# attiny85-mini-mk-2_1.net
KiCad netlist of a schematic drawn in EAGLE
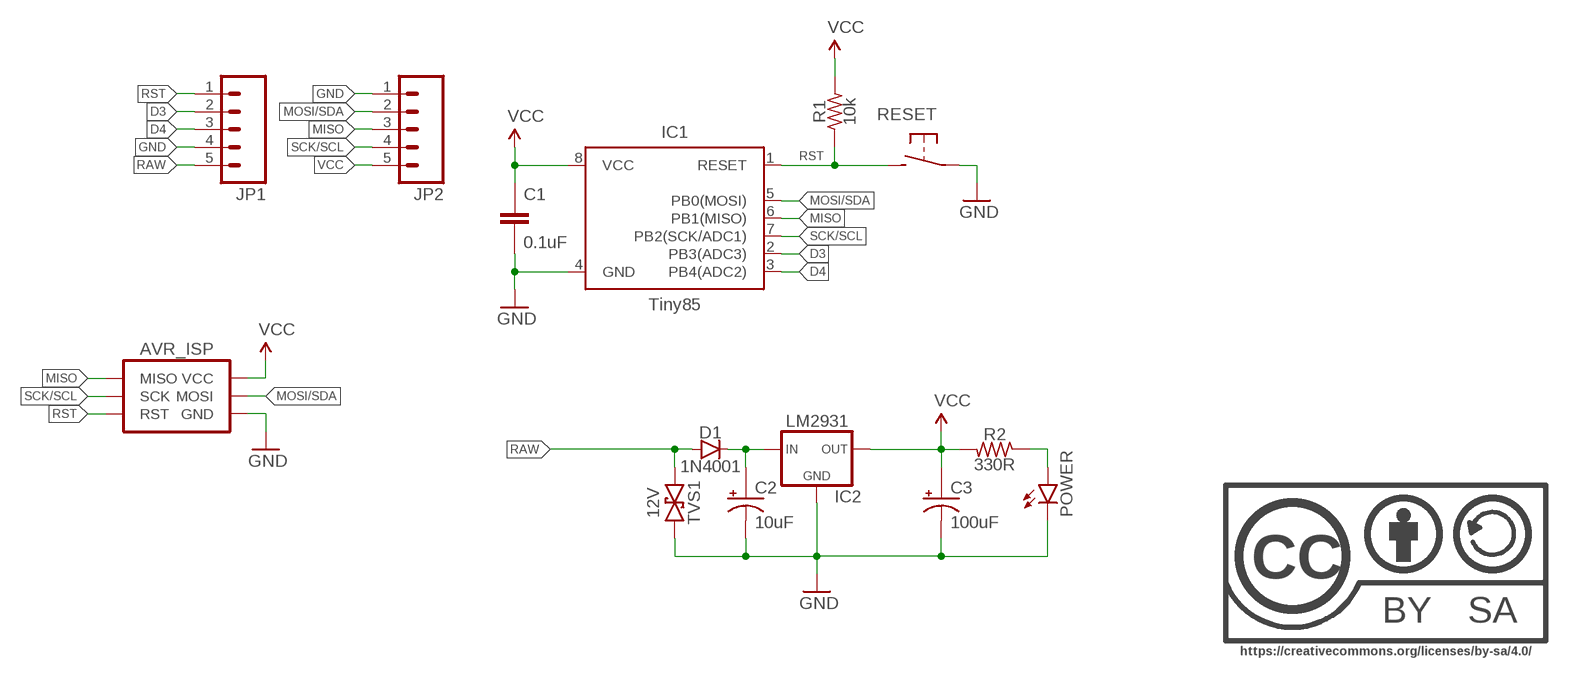
[diagram p0: schematic, sheet 1]

(export (version "E")
  (design (tool "Eeschema 10.0.6"))
  (components
    (comp (ref "AVR_ISP")
      (value "AVR_SPI_PRG_6PTH")
      (footprint "eagle-import:2X3")
      (libsource (lib "eagle-import") (part "AVR_SPI_PRG_6PTH"))
    )
    (comp (ref "C1")
      (value "0.1uF")
      (footprint "eagle-import:C025-024X044")
      (libsource (lib "eagle-import") (part "CAPACITOR-CERAMIC025-024X044"))
    )
    (comp (ref "C2")
      (value "10uF")
      (footprint "eagle-import:E2,5-5")
      (libsource (lib "eagle-import") (part "CAPACITOR-POLARIZEDE2.5-5"))
    )
    (comp (ref "C3")
      (value "100uF")
      (footprint "eagle-import:E2,5-5")
      (libsource (lib "eagle-import") (part "CAPACITOR-POLARIZEDE2.5-5"))
    )
    (comp (ref "D1")
      (value "1N4001")
      (footprint "eagle-import:DIODE-10.16MM")
      (libsource (lib "eagle-import") (part "DIODEPTH-10.68MM"))
    )
    (comp (ref "IC1")
      (value "Tiny85")
      (footprint "eagle-import:DIP08")
      (libsource (lib "eagle-import") (part "ATTINY45TINY85-20-DIP"))
    )
    (comp (ref "IC2")
      (value "LM2931")
      (footprint "eagle-import:TO-92-AMMO")
      (libsource (lib "eagle-import") (part "V_REG_78XXTO-92-INLINE"))
    )
    (comp (ref "JP1")
      (value "M05PTH")
      (footprint "eagle-import:1X05")
      (libsource (lib "eagle-import") (part "M05PTH"))
    )
    (comp (ref "JP2")
      (value "M05PTH")
      (footprint "eagle-import:1X05")
      (libsource (lib "eagle-import") (part "M05PTH"))
    )
    (comp (ref "POWER")
      (value "LED3MM-LESS")
      (footprint "eagle-import:LED3MM-LESSSILK")
      (libsource (lib "eagle-import") (part "LED3MM-LESS"))
    )
    (comp (ref "R1")
      (value "10k")
      (footprint "eagle-import:RESISTOR-AXIAL-PTH-7.62MM")
      (libsource (lib "eagle-import") (part "RESISTORPTH-AXIAL-7.62MM"))
    )
    (comp (ref "R2")
      (value "330R")
      (footprint "eagle-import:RESISTOR-AXIAL-PTH-7.62MM")
      (libsource (lib "eagle-import") (part "RESISTORPTH-AXIAL-7.62MM"))
    )
    (comp (ref "RESET")
      (value "DTS-6MM")
      (footprint "eagle-import:DTS-3-SMALL-PADS")
      (libsource (lib "eagle-import") (part "SPST-NO-TACT3MM-PTH-SMALL-PADS"))
    )
    (comp (ref "TVS1")
      (value "12V")
      (footprint "eagle-import:DO-41-TVS")
      (libsource (lib "eagle-import") (part "TVSDO-41-TVS-BIDIRECTIONAL"))
    )
    (comp (ref "U$1")
      (value "CC-BY-SA-4.0NO-URL")
      (footprint "eagle-import:CC-BY-SA-4.0-NO-URL")
      (libsource (lib "eagle-import") (part "CC-BY-SA-4.0NO-URL"))
    )
  )
  (nets
    (net (code "1") (name "D3") (class "Default")
      (node (ref "IC1") (pin "2") (pinfunction "PB3(ADC3)_2") (pintype "bidirectional"))
      (node (ref "JP1") (pin "2") (pinfunction "2_2") (pintype "passive"))
    )
    (net (code "2") (name "D4") (class "Default")
      (node (ref "IC1") (pin "3") (pinfunction "PB4(ADC2)_3") (pintype "bidirectional"))
      (node (ref "JP1") (pin "3") (pinfunction "3_3") (pintype "passive"))
    )
    (net (code "3") (name "GND") (class "Default")
      (node (ref "AVR_ISP") (pin "6") (pinfunction "GND_6") (pintype "passive"))
      (node (ref "C1") (pin "2") (pinfunction "2_2") (pintype "passive"))
      (node (ref "C2") (pin "-") (pinfunction "-_-") (pintype "passive"))
      (node (ref "C3") (pin "-") (pinfunction "-_-") (pintype "passive"))
      (node (ref "IC1") (pin "4") (pinfunction "GND_4") (pintype "bidirectional"))
      (node (ref "IC2") (pin "2") (pinfunction "GND_2") (pintype "bidirectional"))
      (node (ref "JP1") (pin "4") (pinfunction "4_4") (pintype "passive"))
      (node (ref "JP2") (pin "1") (pinfunction "1_1") (pintype "passive"))
      (node (ref "POWER") (pin "K") (pinfunction "C_K") (pintype "passive"))
      (node (ref "RESET") (pin "1") (pinfunction "1_1") (pintype "passive"))
      (node (ref "TVS1") (pin "P$2") (pinfunction "2_P$2") (pintype "passive"))
    )
    (net (code "4") (name "MISO") (class "Default")
      (node (ref "AVR_ISP") (pin "1") (pinfunction "MISO_1") (pintype "passive"))
      (node (ref "IC1") (pin "6") (pinfunction "PB1(MISO)_6") (pintype "bidirectional"))
      (node (ref "JP2") (pin "3") (pinfunction "3_3") (pintype "passive"))
    )
    (net (code "5") (name "MOSI{slash}SDA") (class "Default")
      (node (ref "AVR_ISP") (pin "4") (pinfunction "MOSI_4") (pintype "passive"))
      (node (ref "IC1") (pin "5") (pinfunction "PB0(MOSI)_5") (pintype "bidirectional"))
      (node (ref "JP2") (pin "2") (pinfunction "2_2") (pintype "passive"))
    )
    (net (code "6") (name "Net-(IC2-IN)") (class "Default")
      (node (ref "C2") (pin "+") (pinfunction "+_+") (pintype "passive"))
      (node (ref "D1") (pin "C") (pinfunction "C_C") (pintype "passive"))
      (node (ref "IC2") (pin "1") (pinfunction "IN_1") (pintype "bidirectional"))
    )
    (net (code "7") (name "Net-(R2-1)") (class "Default")
      (node (ref "POWER") (pin "A") (pinfunction "A_A") (pintype "passive"))
      (node (ref "R2") (pin "P$1") (pinfunction "1_P$1") (pintype "passive"))
    )
    (net (code "8") (name "RAW") (class "Default")
      (node (ref "D1") (pin "A") (pinfunction "A_A") (pintype "passive"))
      (node (ref "JP1") (pin "5") (pinfunction "5_5") (pintype "passive"))
      (node (ref "TVS1") (pin "P$1") (pinfunction "1_P$1") (pintype "passive"))
    )
    (net (code "9") (name "RST") (class "Default")
      (node (ref "AVR_ISP") (pin "5") (pinfunction "RST_5") (pintype "passive"))
      (node (ref "IC1") (pin "1") (pinfunction "RESET_1") (pintype "bidirectional"))
      (node (ref "JP1") (pin "1") (pinfunction "1_1") (pintype "passive"))
      (node (ref "R1") (pin "P$1") (pinfunction "1_P$1") (pintype "passive"))
      (node (ref "RESET") (pin "2") (pinfunction "2_2") (pintype "passive"))
    )
    (net (code "10") (name "SCK{slash}SCL") (class "Default")
      (node (ref "AVR_ISP") (pin "3") (pinfunction "SCK_3") (pintype "passive"))
      (node (ref "IC1") (pin "7") (pinfunction "PB2(SCK/ADC1)_7") (pintype "bidirectional"))
      (node (ref "JP2") (pin "4") (pinfunction "4_4") (pintype "passive"))
    )
    (net (code "11") (name "VCC") (class "Default")
      (node (ref "AVR_ISP") (pin "2") (pinfunction "VCC_2") (pintype "passive"))
      (node (ref "C1") (pin "1") (pinfunction "1_1") (pintype "passive"))
      (node (ref "C3") (pin "+") (pinfunction "+_+") (pintype "passive"))
      (node (ref "IC1") (pin "8") (pinfunction "VCC_8") (pintype "bidirectional"))
      (node (ref "IC2") (pin "3") (pinfunction "OUT_3") (pintype "bidirectional"))
      (node (ref "JP2") (pin "5") (pinfunction "5_5") (pintype "passive"))
      (node (ref "R1") (pin "P$2") (pinfunction "2_P$2") (pintype "passive"))
      (node (ref "R2") (pin "P$2") (pinfunction "2_P$2") (pintype "passive"))
    )
  )
)
